# Sheet2.net
KiCad netlist of a schematic drawn in Altium Designer
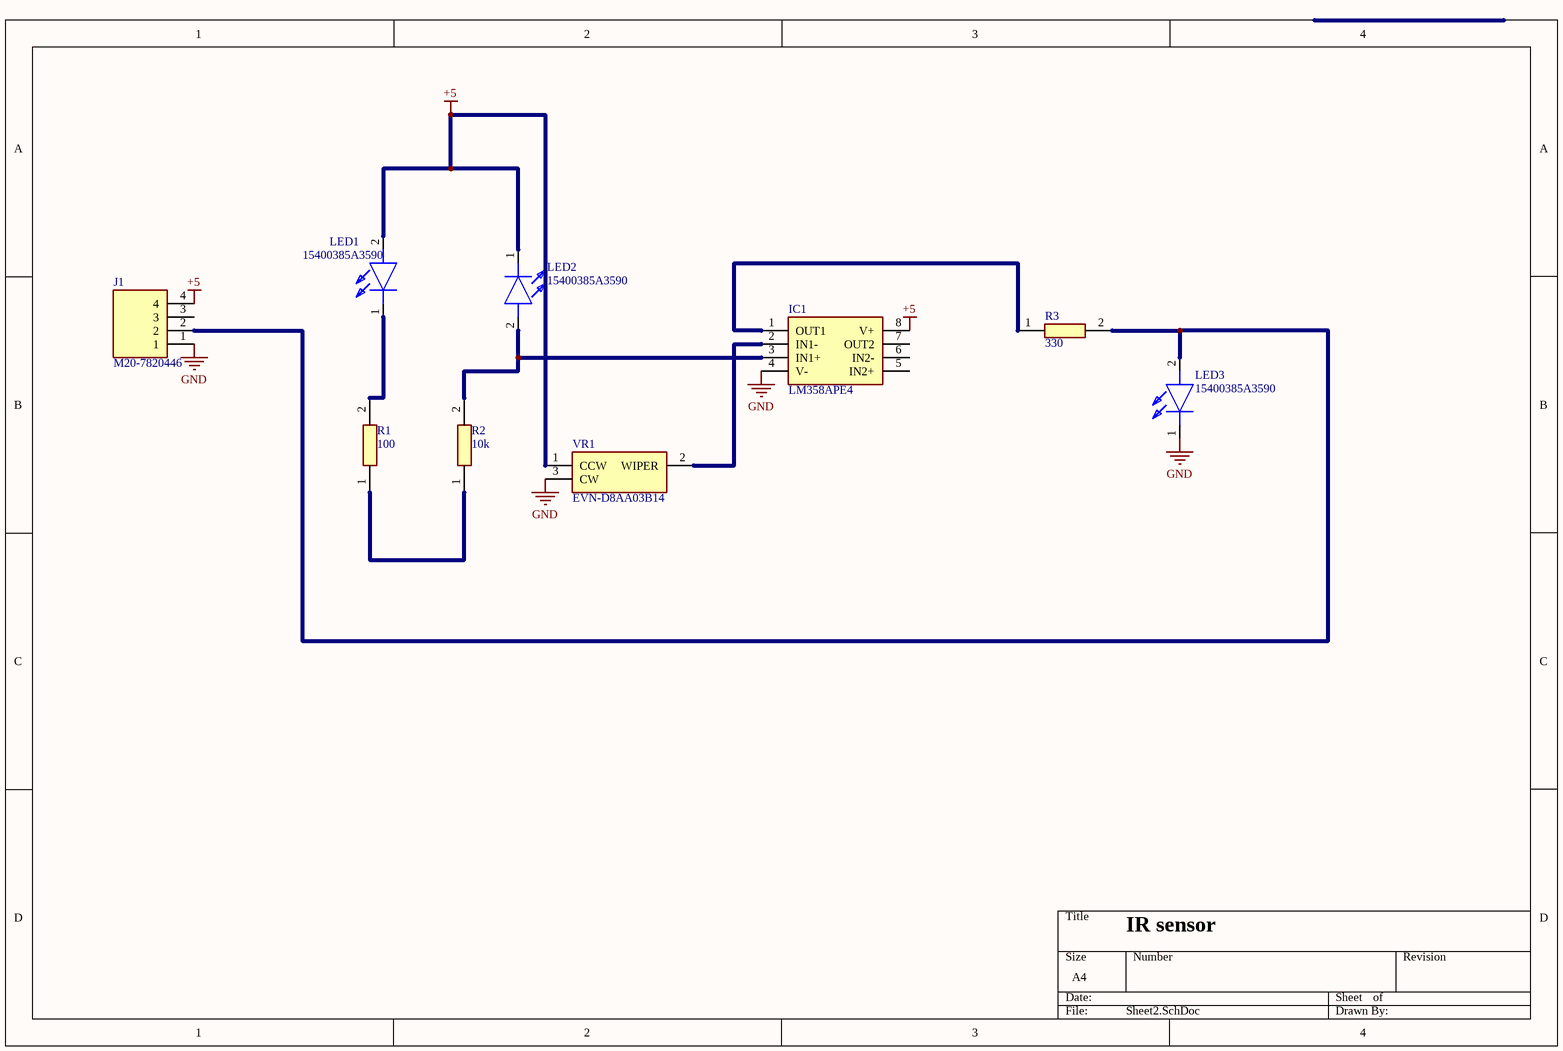
[diagram p0: Sheet2.SchDoc]

(export (version "E")
  (design (tool "Eeschema 10.0.6"))
  (components
    (comp (ref "IC1")
      (value "LM358APE4")
      (footprint "SamacSys:DIP794W53P254L959H508Q8N")
      (description "Integrated Circuit")
      (fields (field (name "MOUSER PART NUMBER") "595-LM358APE4"))
      (libsource (lib "*") (part "LM358APE4"))
    )
    (comp (ref "J1")
      (value "M20-7820446")
      (footprint "SamacSys:RHDR4W70P0X254_1X4_1056X250X865P")
      (description "Connector")
      (fields (field (name "MOUSER PART NUMBER") "855-M20-7820446"))
      (libsource (lib "*") (part "M20-7820446"))
    )
    (comp (ref "LED1")
      (value "15400385A3590")
      (footprint "SamacSys:15400385A3590")
      (description "LED")
      (fields (field (name "MOUSER PART NUMBER") "710-15400385A3590"))
      (libsource (lib "*") (part "15400385A3590"))
    )
    (comp (ref "LED2")
      (value "15400385A3590")
      (footprint "SamacSys:15400385A3590")
      (description "LED")
      (fields (field (name "MOUSER PART NUMBER") "710-15400385A3590"))
      (libsource (lib "*") (part "15400385A3590"))
    )
    (comp (ref "LED3")
      (value "15400385A3590")
      (footprint "SamacSys:15400385A3590")
      (description "LED")
      (fields (field (name "MOUSER PART NUMBER") "710-15400385A3590"))
      (libsource (lib "*") (part "15400385A3590"))
    )
    (comp (ref "R1")
      (value "100")
      (footprint "SamacSys:RESAD1630W60L710D230")
      (description "Resistor")
      (fields
        (field (name "MANUFACTURER_PART_NUMBER") "MF1/4DCT26A1001F")
        (field (name "MOUSER PART NUMBER") "660-MF1/4DCT26A1001F")
      )
      (libsource (lib "SamacSys") (part "MF1_4DCT26A1001F"))
    )
    (comp (ref "R2")
      (value "10k")
      (footprint "SamacSys:RESAD1630W60L710D230")
      (description "Resistor")
      (fields
        (field (name "MANUFACTURER_PART_NUMBER") "MF1/4DCT26A1001F")
        (field (name "MOUSER PART NUMBER") "660-MF1/4DCT26A1001F")
      )
      (libsource (lib "SamacSys") (part "MF1_4DCT26A1001F"))
    )
    (comp (ref "R3")
      (value "330")
      (footprint "SamacSys:RESAD1630W60L710D230")
      (description "Resistor")
      (fields
        (field (name "MANUFACTURER_PART_NUMBER") "MF1/4DCT26A1001F")
        (field (name "MOUSER PART NUMBER") "660-MF1/4DCT26A1001F")
      )
      (libsource (lib "") (part "MF1_4DCT26A1001F_1"))
    )
    (comp (ref "VR1")
      (value "EVN-D8AA03B14")
      (footprint "SamacSys:EVND8AA03B14")
      (description "Variable Resistor")
      (fields (field (name "MOUSER PART NUMBER") "667-EVN-D8AA03B14"))
      (libsource (lib "*") (part "EVN-D8AA03B14"))
    )
  )
  (nets
    (net (code "1") (name "+5") (class "Default")
      (node (ref "IC1") (pin "8") (pinfunction "V+_8") (pintype "passive"))
      (node (ref "J1") (pin "4") (pinfunction "4_4") (pintype "passive"))
      (node (ref "LED1") (pin "2") (pinfunction "A_2") (pintype "passive"))
      (node (ref "LED2") (pin "1") (pinfunction "K_1") (pintype "passive"))
      (node (ref "VR1") (pin "1") (pinfunction "CCW_1") (pintype "passive"))
    )
    (net (code "2") (name "GND") (class "Default")
      (node (ref "IC1") (pin "4") (pinfunction "V-_4") (pintype "passive"))
      (node (ref "J1") (pin "1") (pinfunction "1_1") (pintype "passive"))
      (node (ref "LED3") (pin "1") (pinfunction "K_1") (pintype "passive"))
      (node (ref "VR1") (pin "3") (pinfunction "CW_3") (pintype "passive"))
    )
    (net (code "3") (name "Net-(IC1-IN1+)") (class "Default")
      (node (ref "IC1") (pin "3") (pinfunction "IN1+_3") (pintype "passive"))
      (node (ref "LED2") (pin "2") (pinfunction "A_2") (pintype "passive"))
      (node (ref "R2") (pin "2") (pinfunction "2_2") (pintype "passive"))
    )
    (net (code "4") (name "Net-(IC1-IN1-)") (class "Default")
      (node (ref "IC1") (pin "2") (pinfunction "IN1-_2") (pintype "passive"))
      (node (ref "VR1") (pin "2") (pinfunction "WIPER_2") (pintype "passive"))
    )
    (net (code "5") (name "Net-(IC1-OUT1)") (class "Default")
      (node (ref "IC1") (pin "1") (pinfunction "OUT1_1") (pintype "passive"))
      (node (ref "R3") (pin "1") (pinfunction "1_1") (pintype "passive"))
    )
    (net (code "6") (name "Net-(LED1-K)") (class "Default")
      (node (ref "LED1") (pin "1") (pinfunction "K_1") (pintype "passive"))
      (node (ref "R1") (pin "2") (pinfunction "2_2") (pintype "passive"))
    )
    (net (code "7") (name "Net-(LED3-A)") (class "Default")
      (node (ref "J1") (pin "2") (pinfunction "2_2") (pintype "passive"))
      (node (ref "LED3") (pin "2") (pinfunction "A_2") (pintype "passive"))
      (node (ref "R3") (pin "2") (pinfunction "2_2") (pintype "passive"))
    )
    (net (code "8") (name "Net-(R1-Pad1)") (class "Default")
      (node (ref "R1") (pin "1") (pinfunction "1_1") (pintype "passive"))
      (node (ref "R2") (pin "1") (pinfunction "1_1") (pintype "passive"))
    )
    (net (code "9") (name "unconnected-(IC1-IN2+-Pad5)") (class "Default")
      (node (ref "IC1") (pin "5") (pinfunction "IN2+_5") (pintype "passive"))
    )
    (net (code "10") (name "unconnected-(IC1-IN2--Pad6)") (class "Default")
      (node (ref "IC1") (pin "6") (pinfunction "IN2-_6") (pintype "passive"))
    )
    (net (code "11") (name "unconnected-(IC1-OUT2-Pad7)") (class "Default")
      (node (ref "IC1") (pin "7") (pinfunction "OUT2_7") (pintype "passive"))
    )
    (net (code "12") (name "unconnected-(J1-Pad3)") (class "Default")
      (node (ref "J1") (pin "3") (pinfunction "3_3") (pintype "passive"))
    )
  )
)
